# 10_BUTTONS.net
KiCad netlist of a schematic drawn in Altium Designer
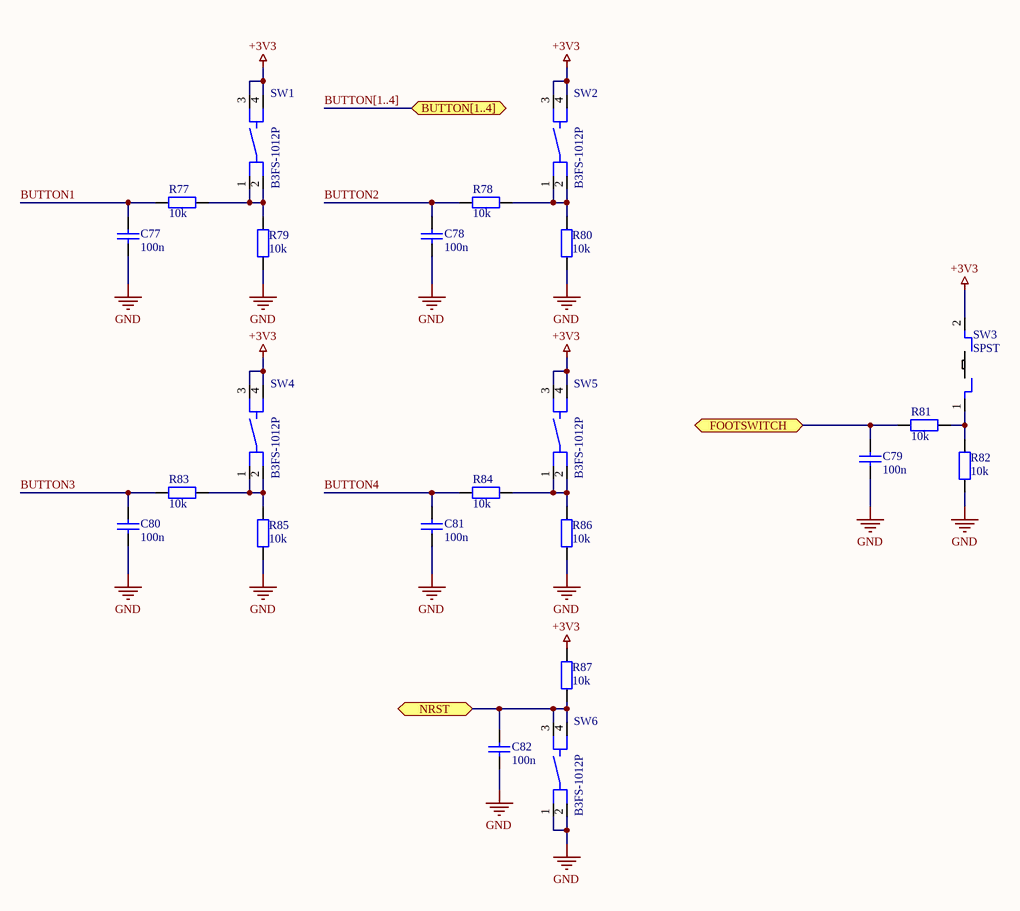
[diagram p0: [10] BUTTONS.SchDoc]

(export (version "E")
  (design (tool "Eeschema 10.0.6"))
  (components
    (comp (ref "C77")
      (value "100n")
      (footprint "STguitar:Capacitor 0603")
      (description "Multilayer Ceramic Capacitors MLCC - SMD/SMT 0603 16VDC 0.1uF 10% X7R")
      (fields
        (field (name "MANUFACTURER PART NUMBER") "EMK107B7104KA-T")
        (field (name "MANUFACTURER") "Taiyo Yuden")
      )
      (libsource (lib "STguitar") (part "Capacitor 100n 10% 0603 EMK107B7104KA-T"))
    )
    (comp (ref "C78")
      (value "100n")
      (footprint "STguitar:Capacitor 0603")
      (description "Multilayer Ceramic Capacitors MLCC - SMD/SMT 0603 16VDC 0.1uF 10% X7R")
      (fields
        (field (name "MANUFACTURER PART NUMBER") "EMK107B7104KA-T")
        (field (name "MANUFACTURER") "Taiyo Yuden")
      )
      (libsource (lib "STguitar") (part "Capacitor 100n 10% 0603 EMK107B7104KA-T"))
    )
    (comp (ref "C79")
      (value "100n")
      (footprint "STguitar:Capacitor 0603")
      (description "Multilayer Ceramic Capacitors MLCC - SMD/SMT 0603 16VDC 0.1uF 10% X7R")
      (fields
        (field (name "MANUFACTURER PART NUMBER") "EMK107B7104KA-T")
        (field (name "MANUFACTURER") "Taiyo Yuden")
      )
      (libsource (lib "STguitar") (part "Capacitor 100n 10% 0603 EMK107B7104KA-T"))
    )
    (comp (ref "C80")
      (value "100n")
      (footprint "STguitar:Capacitor 0603")
      (description "Multilayer Ceramic Capacitors MLCC - SMD/SMT 0603 16VDC 0.1uF 10% X7R")
      (fields
        (field (name "MANUFACTURER PART NUMBER") "EMK107B7104KA-T")
        (field (name "MANUFACTURER") "Taiyo Yuden")
      )
      (libsource (lib "STguitar") (part "Capacitor 100n 10% 0603 EMK107B7104KA-T"))
    )
    (comp (ref "C81")
      (value "100n")
      (footprint "STguitar:Capacitor 0603")
      (description "Multilayer Ceramic Capacitors MLCC - SMD/SMT 0603 16VDC 0.1uF 10% X7R")
      (fields
        (field (name "MANUFACTURER PART NUMBER") "EMK107B7104KA-T")
        (field (name "MANUFACTURER") "Taiyo Yuden")
      )
      (libsource (lib "STguitar") (part "Capacitor 100n 10% 0603 EMK107B7104KA-T"))
    )
    (comp (ref "C82")
      (value "100n")
      (footprint "STguitar:Capacitor 0603")
      (description "Multilayer Ceramic Capacitors MLCC - SMD/SMT 0603 16VDC 0.1uF 10% X7R")
      (fields
        (field (name "MANUFACTURER PART NUMBER") "EMK107B7104KA-T")
        (field (name "MANUFACTURER") "Taiyo Yuden")
      )
      (libsource (lib "STguitar") (part "Capacitor 100n 10% 0603 EMK107B7104KA-T"))
    )
    (comp (ref "R77")
      (value "10k")
      (footprint "STguitar:Resistor 0603")
      (description "Thin Film Resistors - SMD 10K ohm 1% 1/10W")
      (fields
        (field (name "MANUFACTURER PART NUMBER") "RT0603FRE0710KL")
        (field (name "MANUFACTURER") "Yageo")
      )
      (libsource (lib "") (part "Resistor 10k 1% 0603 RT0603FRE0710KL_1"))
    )
    (comp (ref "R78")
      (value "10k")
      (footprint "STguitar:Resistor 0603")
      (description "Thin Film Resistors - SMD 10K ohm 1% 1/10W")
      (fields
        (field (name "MANUFACTURER PART NUMBER") "RT0603FRE0710KL")
        (field (name "MANUFACTURER") "Yageo")
      )
      (libsource (lib "") (part "Resistor 10k 1% 0603 RT0603FRE0710KL_1"))
    )
    (comp (ref "R79")
      (value "10k")
      (footprint "STguitar:Resistor 0603")
      (description "Thin Film Resistors - SMD 10K ohm 1% 1/10W")
      (fields
        (field (name "MANUFACTURER PART NUMBER") "RT0603FRE0710KL")
        (field (name "MANUFACTURER") "Yageo")
      )
      (libsource (lib "STguitar") (part "Resistor 10k 1% 0603 RT0603FRE0710KL"))
    )
    (comp (ref "R80")
      (value "10k")
      (footprint "STguitar:Resistor 0603")
      (description "Thin Film Resistors - SMD 10K ohm 1% 1/10W")
      (fields
        (field (name "MANUFACTURER PART NUMBER") "RT0603FRE0710KL")
        (field (name "MANUFACTURER") "Yageo")
      )
      (libsource (lib "STguitar") (part "Resistor 10k 1% 0603 RT0603FRE0710KL"))
    )
    (comp (ref "R81")
      (value "10k")
      (footprint "STguitar:Resistor 0603")
      (description "Thin Film Resistors - SMD 10K ohm 1% 1/10W")
      (fields
        (field (name "MANUFACTURER PART NUMBER") "RT0603FRE0710KL")
        (field (name "MANUFACTURER") "Yageo")
      )
      (libsource (lib "") (part "Resistor 10k 1% 0603 RT0603FRE0710KL_1"))
    )
    (comp (ref "R82")
      (value "10k")
      (footprint "STguitar:Resistor 0603")
      (description "Thin Film Resistors - SMD 10K ohm 1% 1/10W")
      (fields
        (field (name "MANUFACTURER PART NUMBER") "RT0603FRE0710KL")
        (field (name "MANUFACTURER") "Yageo")
      )
      (libsource (lib "STguitar") (part "Resistor 10k 1% 0603 RT0603FRE0710KL"))
    )
    (comp (ref "R83")
      (value "10k")
      (footprint "STguitar:Resistor 0603")
      (description "Thin Film Resistors - SMD 10K ohm 1% 1/10W")
      (fields
        (field (name "MANUFACTURER PART NUMBER") "RT0603FRE0710KL")
        (field (name "MANUFACTURER") "Yageo")
      )
      (libsource (lib "") (part "Resistor 10k 1% 0603 RT0603FRE0710KL_1"))
    )
    (comp (ref "R84")
      (value "10k")
      (footprint "STguitar:Resistor 0603")
      (description "Thin Film Resistors - SMD 10K ohm 1% 1/10W")
      (fields
        (field (name "MANUFACTURER PART NUMBER") "RT0603FRE0710KL")
        (field (name "MANUFACTURER") "Yageo")
      )
      (libsource (lib "") (part "Resistor 10k 1% 0603 RT0603FRE0710KL_1"))
    )
    (comp (ref "R85")
      (value "10k")
      (footprint "STguitar:Resistor 0603")
      (description "Thin Film Resistors - SMD 10K ohm 1% 1/10W")
      (fields
        (field (name "MANUFACTURER PART NUMBER") "RT0603FRE0710KL")
        (field (name "MANUFACTURER") "Yageo")
      )
      (libsource (lib "STguitar") (part "Resistor 10k 1% 0603 RT0603FRE0710KL"))
    )
    (comp (ref "R86")
      (value "10k")
      (footprint "STguitar:Resistor 0603")
      (description "Thin Film Resistors - SMD 10K ohm 1% 1/10W")
      (fields
        (field (name "MANUFACTURER PART NUMBER") "RT0603FRE0710KL")
        (field (name "MANUFACTURER") "Yageo")
      )
      (libsource (lib "STguitar") (part "Resistor 10k 1% 0603 RT0603FRE0710KL"))
    )
    (comp (ref "R87")
      (value "10k")
      (footprint "STguitar:Resistor 0603")
      (description "Thin Film Resistors - SMD 10K ohm 1% 1/10W")
      (fields
        (field (name "MANUFACTURER PART NUMBER") "RT0603FRE0710KL")
        (field (name "MANUFACTURER") "Yageo")
      )
      (libsource (lib "STguitar") (part "Resistor 10k 1% 0603 RT0603FRE0710KL"))
    )
    (comp (ref "SW1")
      (value "B3FS-1012P")
      (footprint "STguitar:Mechanical Tacitile 6x6")
      (description "Tactile Switches Tactile Switch")
      (fields (field (name "MANUFACTURER") "Omron Electronics"))
      (libsource (lib "STguitar") (part "Mechanical Tactile Switches Tactile Switch B3FS-1012P"))
    )
    (comp (ref "SW2")
      (value "B3FS-1012P")
      (footprint "STguitar:Mechanical Tacitile 6x6")
      (description "Tactile Switches Tactile Switch")
      (fields (field (name "MANUFACTURER") "Omron Electronics"))
      (libsource (lib "STguitar") (part "Mechanical Tactile Switches Tactile Switch B3FS-1012P"))
    )
    (comp (ref "SW3")
      (value "SPST")
      (footprint "STguitar:Mechanical footswitch SPST")
      (description "Pushbutton Switches SP ON-OFF SOLDER LUG")
      (fields
        (field (name "MANUFACTURER PART NUMBER") "64111210")
        (field (name "MANUFACTURER") "Carling Technologies")
      )
      (libsource (lib "STguitar") (part "Mechanical Pushbutton Switches SP ON-OFF SOLDER LUG"))
    )
    (comp (ref "SW4")
      (value "B3FS-1012P")
      (footprint "STguitar:Mechanical Tacitile 6x6")
      (description "Tactile Switches Tactile Switch")
      (fields (field (name "MANUFACTURER") "Omron Electronics"))
      (libsource (lib "STguitar") (part "Mechanical Tactile Switches Tactile Switch B3FS-1012P"))
    )
    (comp (ref "SW5")
      (value "B3FS-1012P")
      (footprint "STguitar:Mechanical Tacitile 6x6")
      (description "Tactile Switches Tactile Switch")
      (fields (field (name "MANUFACTURER") "Omron Electronics"))
      (libsource (lib "STguitar") (part "Mechanical Tactile Switches Tactile Switch B3FS-1012P"))
    )
    (comp (ref "SW6")
      (value "B3FS-1012P")
      (footprint "STguitar:Mechanical Tacitile 6x6")
      (description "Tactile Switches Tactile Switch")
      (fields (field (name "MANUFACTURER") "Omron Electronics"))
      (libsource (lib "STguitar") (part "Mechanical Tactile Switches Tactile Switch B3FS-1012P"))
    )
  )
  (nets
    (net (code "1") (name "+3V3") (class "Default")
      (node (ref "R87") (pin "2") (pinfunction "2_2") (pintype "passive"))
      (node (ref "SW1") (pin "3") (pinfunction "3_3") (pintype "passive"))
      (node (ref "SW1") (pin "4") (pinfunction "4_4") (pintype "passive"))
      (node (ref "SW2") (pin "3") (pinfunction "3_3") (pintype "passive"))
      (node (ref "SW2") (pin "4") (pinfunction "4_4") (pintype "passive"))
      (node (ref "SW3") (pin "2") (pinfunction "2_2") (pintype "passive"))
      (node (ref "SW4") (pin "3") (pinfunction "3_3") (pintype "passive"))
      (node (ref "SW4") (pin "4") (pinfunction "4_4") (pintype "passive"))
      (node (ref "SW5") (pin "3") (pinfunction "3_3") (pintype "passive"))
      (node (ref "SW5") (pin "4") (pinfunction "4_4") (pintype "passive"))
    )
    (net (code "2") (name "/BUTTON1") (class "Default")
      (node (ref "C77") (pin "2") (pinfunction "2_2") (pintype "passive"))
      (node (ref "R77") (pin "2") (pinfunction "2_2") (pintype "passive"))
    )
    (net (code "3") (name "/BUTTON2") (class "Default")
      (node (ref "C78") (pin "2") (pinfunction "2_2") (pintype "passive"))
      (node (ref "R78") (pin "2") (pinfunction "2_2") (pintype "passive"))
    )
    (net (code "4") (name "/BUTTON3") (class "Default")
      (node (ref "C80") (pin "2") (pinfunction "2_2") (pintype "passive"))
      (node (ref "R83") (pin "2") (pinfunction "2_2") (pintype "passive"))
    )
    (net (code "5") (name "/BUTTON4") (class "Default")
      (node (ref "C81") (pin "2") (pinfunction "2_2") (pintype "passive"))
      (node (ref "R84") (pin "2") (pinfunction "2_2") (pintype "passive"))
    )
    (net (code "7") (name "/FOOTSWITCH") (class "Default")
      (node (ref "C79") (pin "2") (pinfunction "2_2") (pintype "passive"))
      (node (ref "R81") (pin "2") (pinfunction "2_2") (pintype "passive"))
    )
    (net (code "8") (name "/NRST") (class "Default")
      (node (ref "C82") (pin "2") (pinfunction "2_2") (pintype "passive"))
      (node (ref "R87") (pin "1") (pinfunction "1_1") (pintype "passive"))
      (node (ref "SW6") (pin "3") (pinfunction "3_3") (pintype "passive"))
      (node (ref "SW6") (pin "4") (pinfunction "4_4") (pintype "passive"))
    )
    (net (code "9") (name "GND") (class "Default")
      (node (ref "C77") (pin "1") (pinfunction "1_1") (pintype "passive"))
      (node (ref "C78") (pin "1") (pinfunction "1_1") (pintype "passive"))
      (node (ref "C79") (pin "1") (pinfunction "1_1") (pintype "passive"))
      (node (ref "C80") (pin "1") (pinfunction "1_1") (pintype "passive"))
      (node (ref "C81") (pin "1") (pinfunction "1_1") (pintype "passive"))
      (node (ref "C82") (pin "1") (pinfunction "1_1") (pintype "passive"))
      (node (ref "R79") (pin "1") (pinfunction "1_1") (pintype "passive"))
      (node (ref "R80") (pin "1") (pinfunction "1_1") (pintype "passive"))
      (node (ref "R82") (pin "1") (pinfunction "1_1") (pintype "passive"))
      (node (ref "R85") (pin "1") (pinfunction "1_1") (pintype "passive"))
      (node (ref "R86") (pin "1") (pinfunction "1_1") (pintype "passive"))
      (node (ref "SW6") (pin "1") (pinfunction "1_1") (pintype "passive"))
      (node (ref "SW6") (pin "2") (pinfunction "2_2") (pintype "passive"))
    )
    (net (code "10") (name "Net-(R77-Pad1)") (class "Default")
      (node (ref "R77") (pin "1") (pinfunction "1_1") (pintype "passive"))
      (node (ref "R79") (pin "2") (pinfunction "2_2") (pintype "passive"))
      (node (ref "SW1") (pin "1") (pinfunction "1_1") (pintype "passive"))
      (node (ref "SW1") (pin "2") (pinfunction "2_2") (pintype "passive"))
    )
    (net (code "11") (name "Net-(R78-Pad1)") (class "Default")
      (node (ref "R78") (pin "1") (pinfunction "1_1") (pintype "passive"))
      (node (ref "R80") (pin "2") (pinfunction "2_2") (pintype "passive"))
      (node (ref "SW2") (pin "1") (pinfunction "1_1") (pintype "passive"))
      (node (ref "SW2") (pin "2") (pinfunction "2_2") (pintype "passive"))
    )
    (net (code "12") (name "Net-(R81-Pad1)") (class "Default")
      (node (ref "R81") (pin "1") (pinfunction "1_1") (pintype "passive"))
      (node (ref "R82") (pin "2") (pinfunction "2_2") (pintype "passive"))
      (node (ref "SW3") (pin "1") (pinfunction "1_1") (pintype "passive"))
    )
    (net (code "13") (name "Net-(R83-Pad1)") (class "Default")
      (node (ref "R83") (pin "1") (pinfunction "1_1") (pintype "passive"))
      (node (ref "R85") (pin "2") (pinfunction "2_2") (pintype "passive"))
      (node (ref "SW4") (pin "1") (pinfunction "1_1") (pintype "passive"))
      (node (ref "SW4") (pin "2") (pinfunction "2_2") (pintype "passive"))
    )
    (net (code "14") (name "Net-(R84-Pad1)") (class "Default")
      (node (ref "R84") (pin "1") (pinfunction "1_1") (pintype "passive"))
      (node (ref "R86") (pin "2") (pinfunction "2_2") (pintype "passive"))
      (node (ref "SW5") (pin "1") (pinfunction "1_1") (pintype "passive"))
      (node (ref "SW5") (pin "2") (pinfunction "2_2") (pintype "passive"))
    )
  )
)
